# 1-Schematic_RGB_SENSOR_PEN.net
KiCad netlist of a schematic drawn in EasyEDA
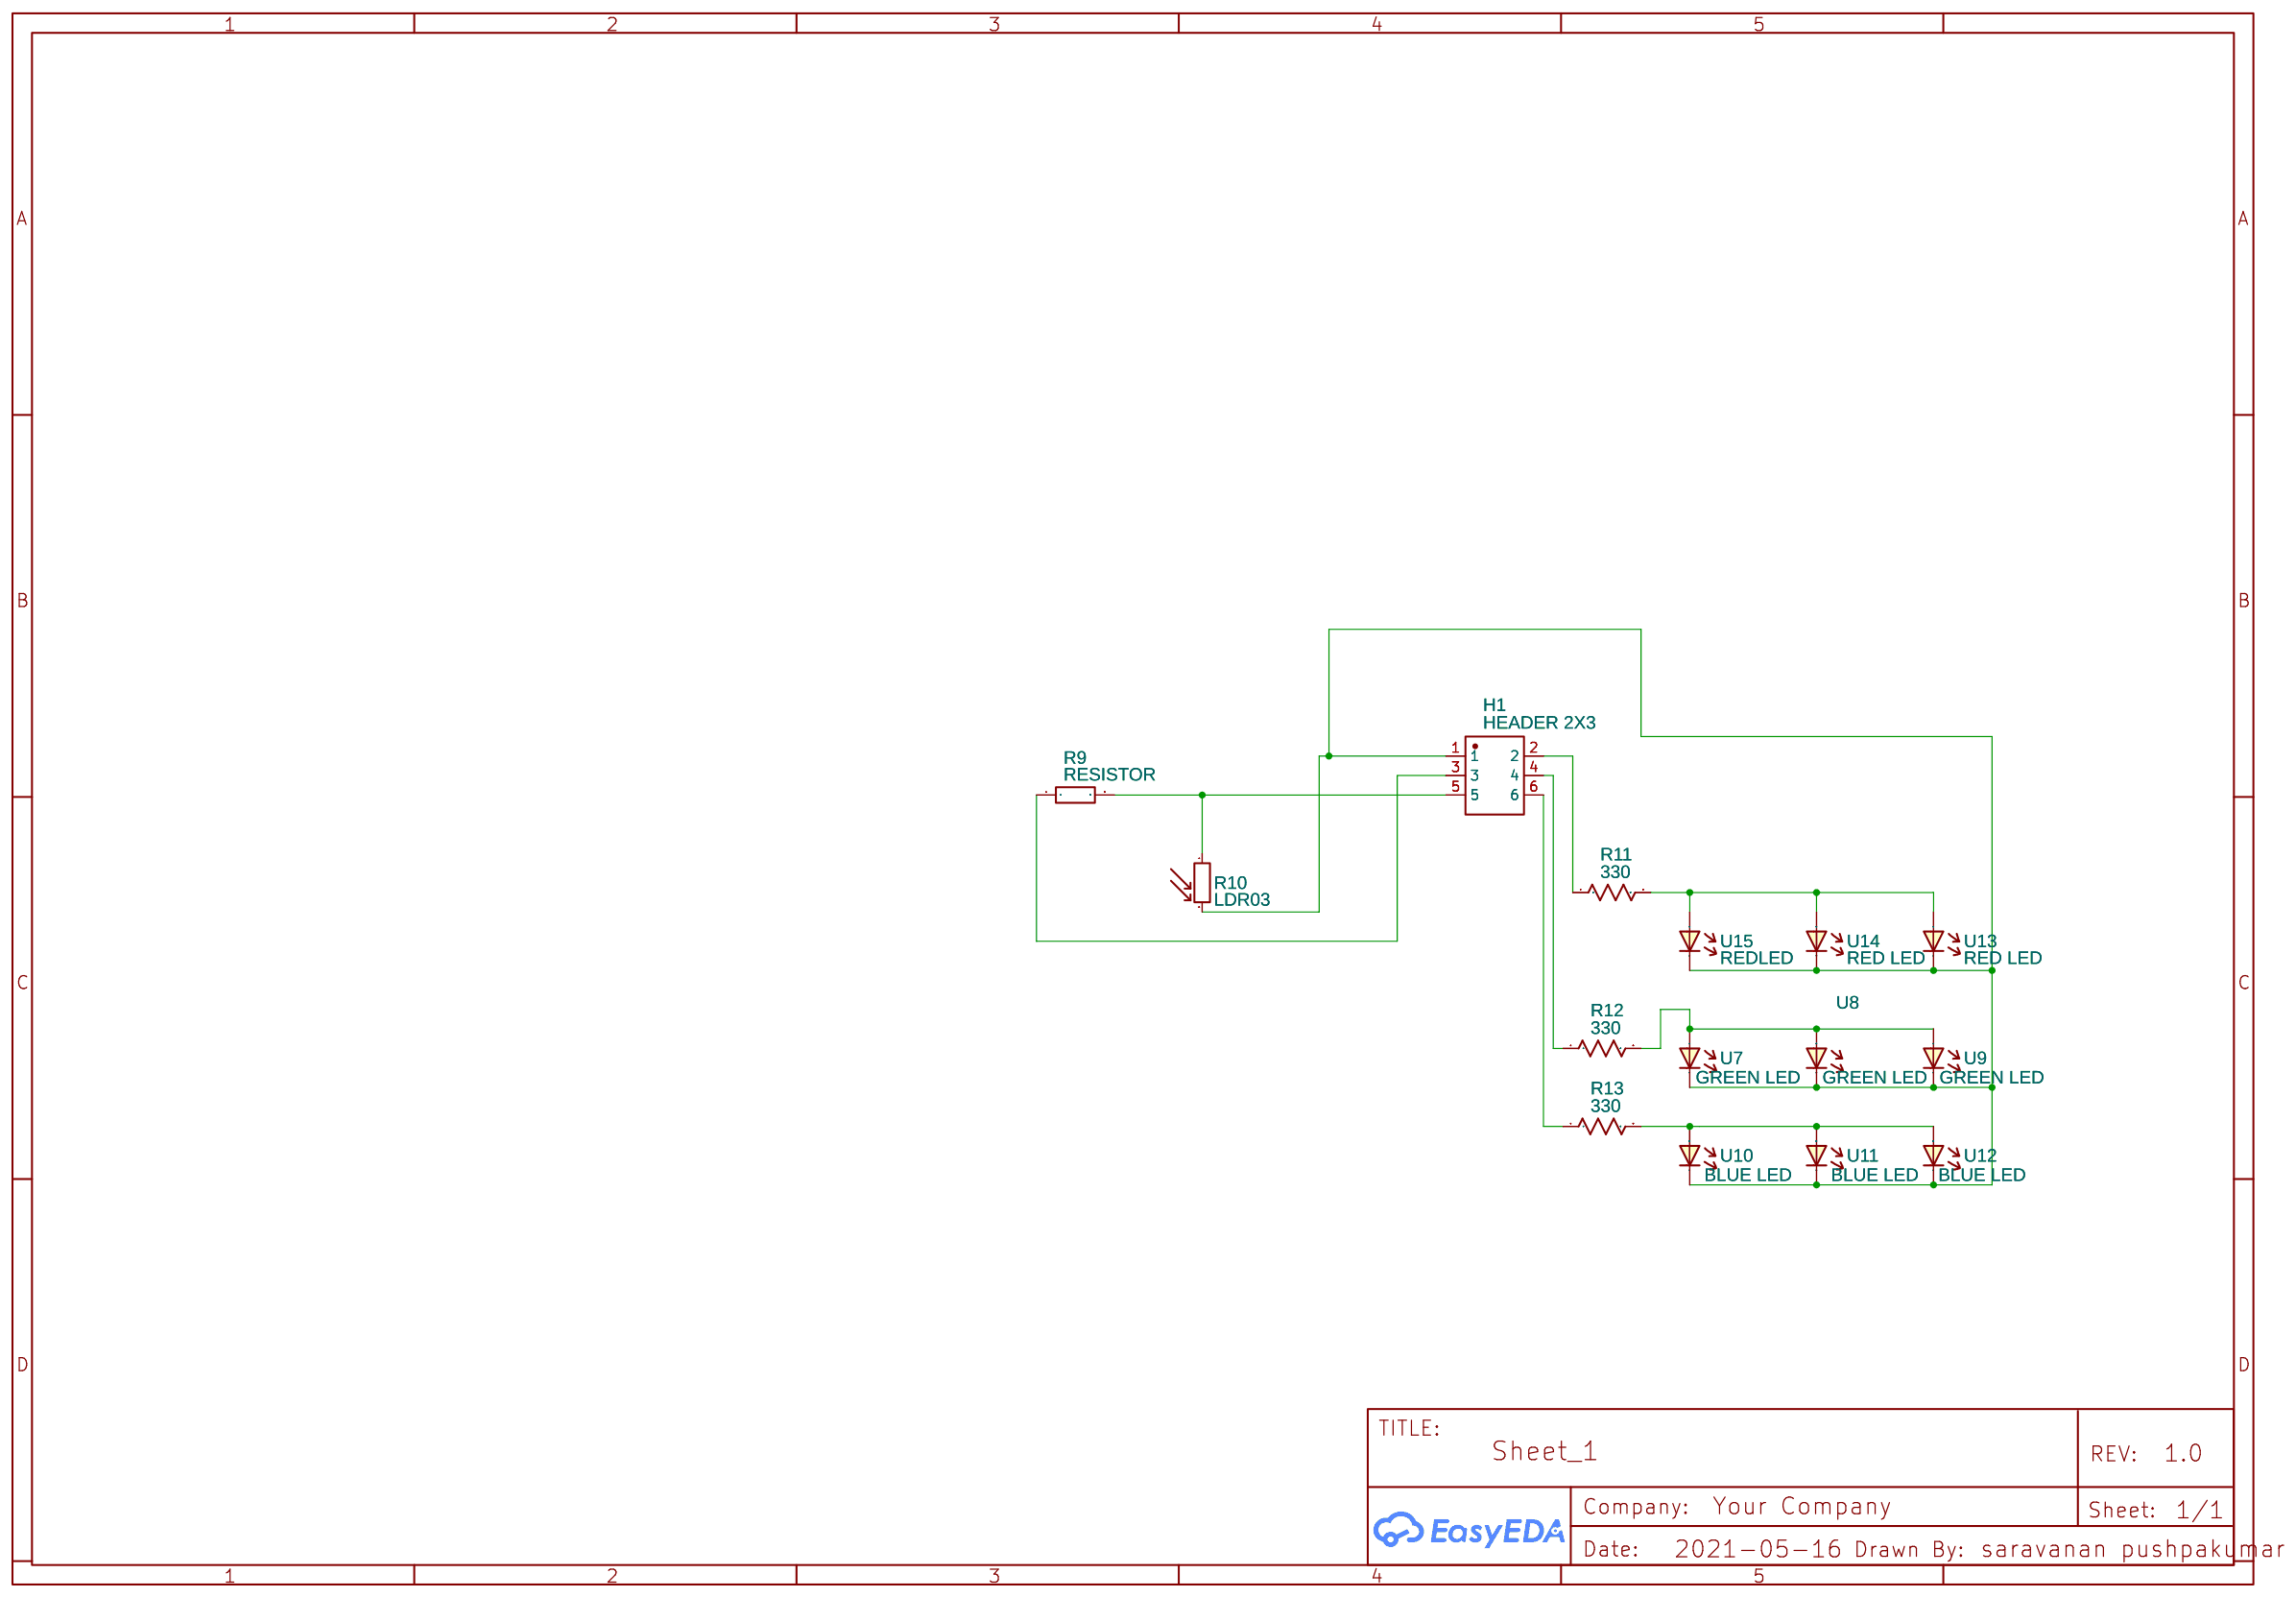
[diagram p0: schematic sheet]

(export (version "E")
  (design (tool "Eeschema 10.0.6"))
  (components
    (comp (ref "H1")
      (value "HEADER 2X3")
      (fields
        (field (name "BOM_Manufacturer Part") "Female header/2.54mm2x3 Female header")
        (field (name "BOM_Supplier Part") "C47552")
      )
      (libsource (lib "") (part "HEADER 2X3"))
    )
    (comp (ref "R9")
      (value "RESISTOR")
      (fields
        (field (name "BOM_Manufacturer Part") "MFR0W4F2200A50")
        (field (name "BOM_Supplier Part") "E57439")
      )
      (libsource (lib "") (part "RESISTOR"))
    )
    (comp (ref "R10") (value "LDR03") (libsource (lib "") (part "LDR03")))
    (comp (ref "R11")
      (value "330")
      (fields
        (field (name "BOM_Manufacturer Part") "MCF 0.25W 120R")
        (field (name "BOM_Supplier Part") "9339116")
      )
      (libsource (lib "") (part "330"))
    )
    (comp (ref "R12")
      (value "330")
      (fields
        (field (name "BOM_Manufacturer Part") "MCF 0.25W 120R")
        (field (name "BOM_Supplier Part") "9339116")
      )
      (libsource (lib "") (part "330"))
    )
    (comp (ref "R13")
      (value "330")
      (fields
        (field (name "BOM_Manufacturer Part") "MCF 0.25W 120R")
        (field (name "BOM_Supplier Part") "9339116")
      )
      (libsource (lib "") (part "330"))
    )
    (comp (ref "U7")
      (value "GREEN LED")
      (fields (field (name "BOM_Manufacturer Part") "5mm LED"))
      (libsource (lib "") (part "LED"))
    )
    (comp (ref "U8")
      (value "GREEN LED")
      (fields (field (name "BOM_Manufacturer Part") "5mm LED"))
      (libsource (lib "") (part "LED"))
    )
    (comp (ref "U9")
      (value "GREEN LED")
      (fields (field (name "BOM_Manufacturer Part") "5mm LED"))
      (libsource (lib "") (part "LED"))
    )
    (comp (ref "U10")
      (value "BLUE LED")
      (fields (field (name "BOM_Manufacturer Part") "5mm LED"))
      (libsource (lib "") (part "LED"))
    )
    (comp (ref "U11")
      (value "BLUE LED")
      (fields (field (name "BOM_Manufacturer Part") "5mm LED"))
      (libsource (lib "") (part "LED"))
    )
    (comp (ref "U12")
      (value "BLUE LED")
      (fields (field (name "BOM_Manufacturer Part") "5mm LED"))
      (libsource (lib "") (part "LED"))
    )
    (comp (ref "U13")
      (value "RED LED")
      (fields (field (name "BOM_Manufacturer Part") "5mm LED"))
      (libsource (lib "") (part "LED"))
    )
    (comp (ref "U14")
      (value "RED LED")
      (fields (field (name "BOM_Manufacturer Part") "5mm LED"))
      (libsource (lib "") (part "LED"))
    )
    (comp (ref "U15")
      (value "REDLED")
      (fields (field (name "BOM_Manufacturer Part") "5mm LED"))
      (libsource (lib "") (part "LED"))
    )
  )
  (nets
    (net (code "1") (name "Net-(H1-Pad1)") (class "Default")
      (node (ref "H1") (pin "1") (pinfunction "1_1") (pintype "unspecified"))
      (node (ref "R10") (pin "2") (pintype "unspecified"))
      (node (ref "U10") (pin "2") (pinfunction "2_2") (pintype "unspecified"))
      (node (ref "U11") (pin "2") (pinfunction "2_2") (pintype "unspecified"))
      (node (ref "U12") (pin "2") (pinfunction "2_2") (pintype "unspecified"))
      (node (ref "U13") (pin "2") (pinfunction "2_2") (pintype "unspecified"))
      (node (ref "U14") (pin "2") (pinfunction "2_2") (pintype "unspecified"))
      (node (ref "U15") (pin "2") (pinfunction "2_2") (pintype "unspecified"))
      (node (ref "U7") (pin "2") (pinfunction "2_2") (pintype "unspecified"))
      (node (ref "U8") (pin "2") (pinfunction "2_2") (pintype "unspecified"))
      (node (ref "U9") (pin "2") (pinfunction "2_2") (pintype "unspecified"))
    )
    (net (code "2") (name "Net-(H1-Pad2)") (class "Default")
      (node (ref "H1") (pin "2") (pinfunction "2_2") (pintype "unspecified"))
      (node (ref "R11") (pin "1") (pinfunction "1_1") (pintype "unspecified"))
    )
    (net (code "3") (name "Net-(H1-Pad3)") (class "Default")
      (node (ref "H1") (pin "3") (pinfunction "3_3") (pintype "unspecified"))
      (node (ref "R9") (pin "1") (pinfunction "1_1") (pintype "input"))
    )
    (net (code "4") (name "Net-(H1-Pad4)") (class "Default")
      (node (ref "H1") (pin "4") (pinfunction "4_4") (pintype "unspecified"))
      (node (ref "R12") (pin "1") (pinfunction "1_1") (pintype "unspecified"))
    )
    (net (code "5") (name "Net-(H1-Pad5)") (class "Default")
      (node (ref "H1") (pin "5") (pinfunction "5_5") (pintype "unspecified"))
      (node (ref "R10") (pin "1") (pintype "unspecified"))
      (node (ref "R9") (pin "2") (pinfunction "2_2") (pintype "input"))
    )
    (net (code "6") (name "Net-(H1-Pad6)") (class "Default")
      (node (ref "H1") (pin "6") (pinfunction "6_6") (pintype "unspecified"))
      (node (ref "R13") (pin "1") (pinfunction "1_1") (pintype "unspecified"))
    )
    (net (code "7") (name "Net-(R11-Pad2)") (class "Default")
      (node (ref "R11") (pin "2") (pinfunction "2_2") (pintype "unspecified"))
      (node (ref "U13") (pin "1") (pinfunction "1_1") (pintype "unspecified"))
      (node (ref "U14") (pin "1") (pinfunction "1_1") (pintype "unspecified"))
      (node (ref "U15") (pin "1") (pinfunction "1_1") (pintype "unspecified"))
    )
    (net (code "8") (name "Net-(R12-Pad2)") (class "Default")
      (node (ref "R12") (pin "2") (pinfunction "2_2") (pintype "unspecified"))
      (node (ref "U7") (pin "1") (pinfunction "1_1") (pintype "unspecified"))
      (node (ref "U8") (pin "1") (pinfunction "1_1") (pintype "unspecified"))
      (node (ref "U9") (pin "1") (pinfunction "1_1") (pintype "unspecified"))
    )
    (net (code "9") (name "Net-(R13-Pad2)") (class "Default")
      (node (ref "R13") (pin "2") (pinfunction "2_2") (pintype "unspecified"))
      (node (ref "U10") (pin "1") (pinfunction "1_1") (pintype "unspecified"))
      (node (ref "U11") (pin "1") (pinfunction "1_1") (pintype "unspecified"))
      (node (ref "U12") (pin "1") (pinfunction "1_1") (pintype "unspecified"))
    )
  )
)
